# mspfacedraft3.net
KiCad netlist of a schematic drawn in EAGLE
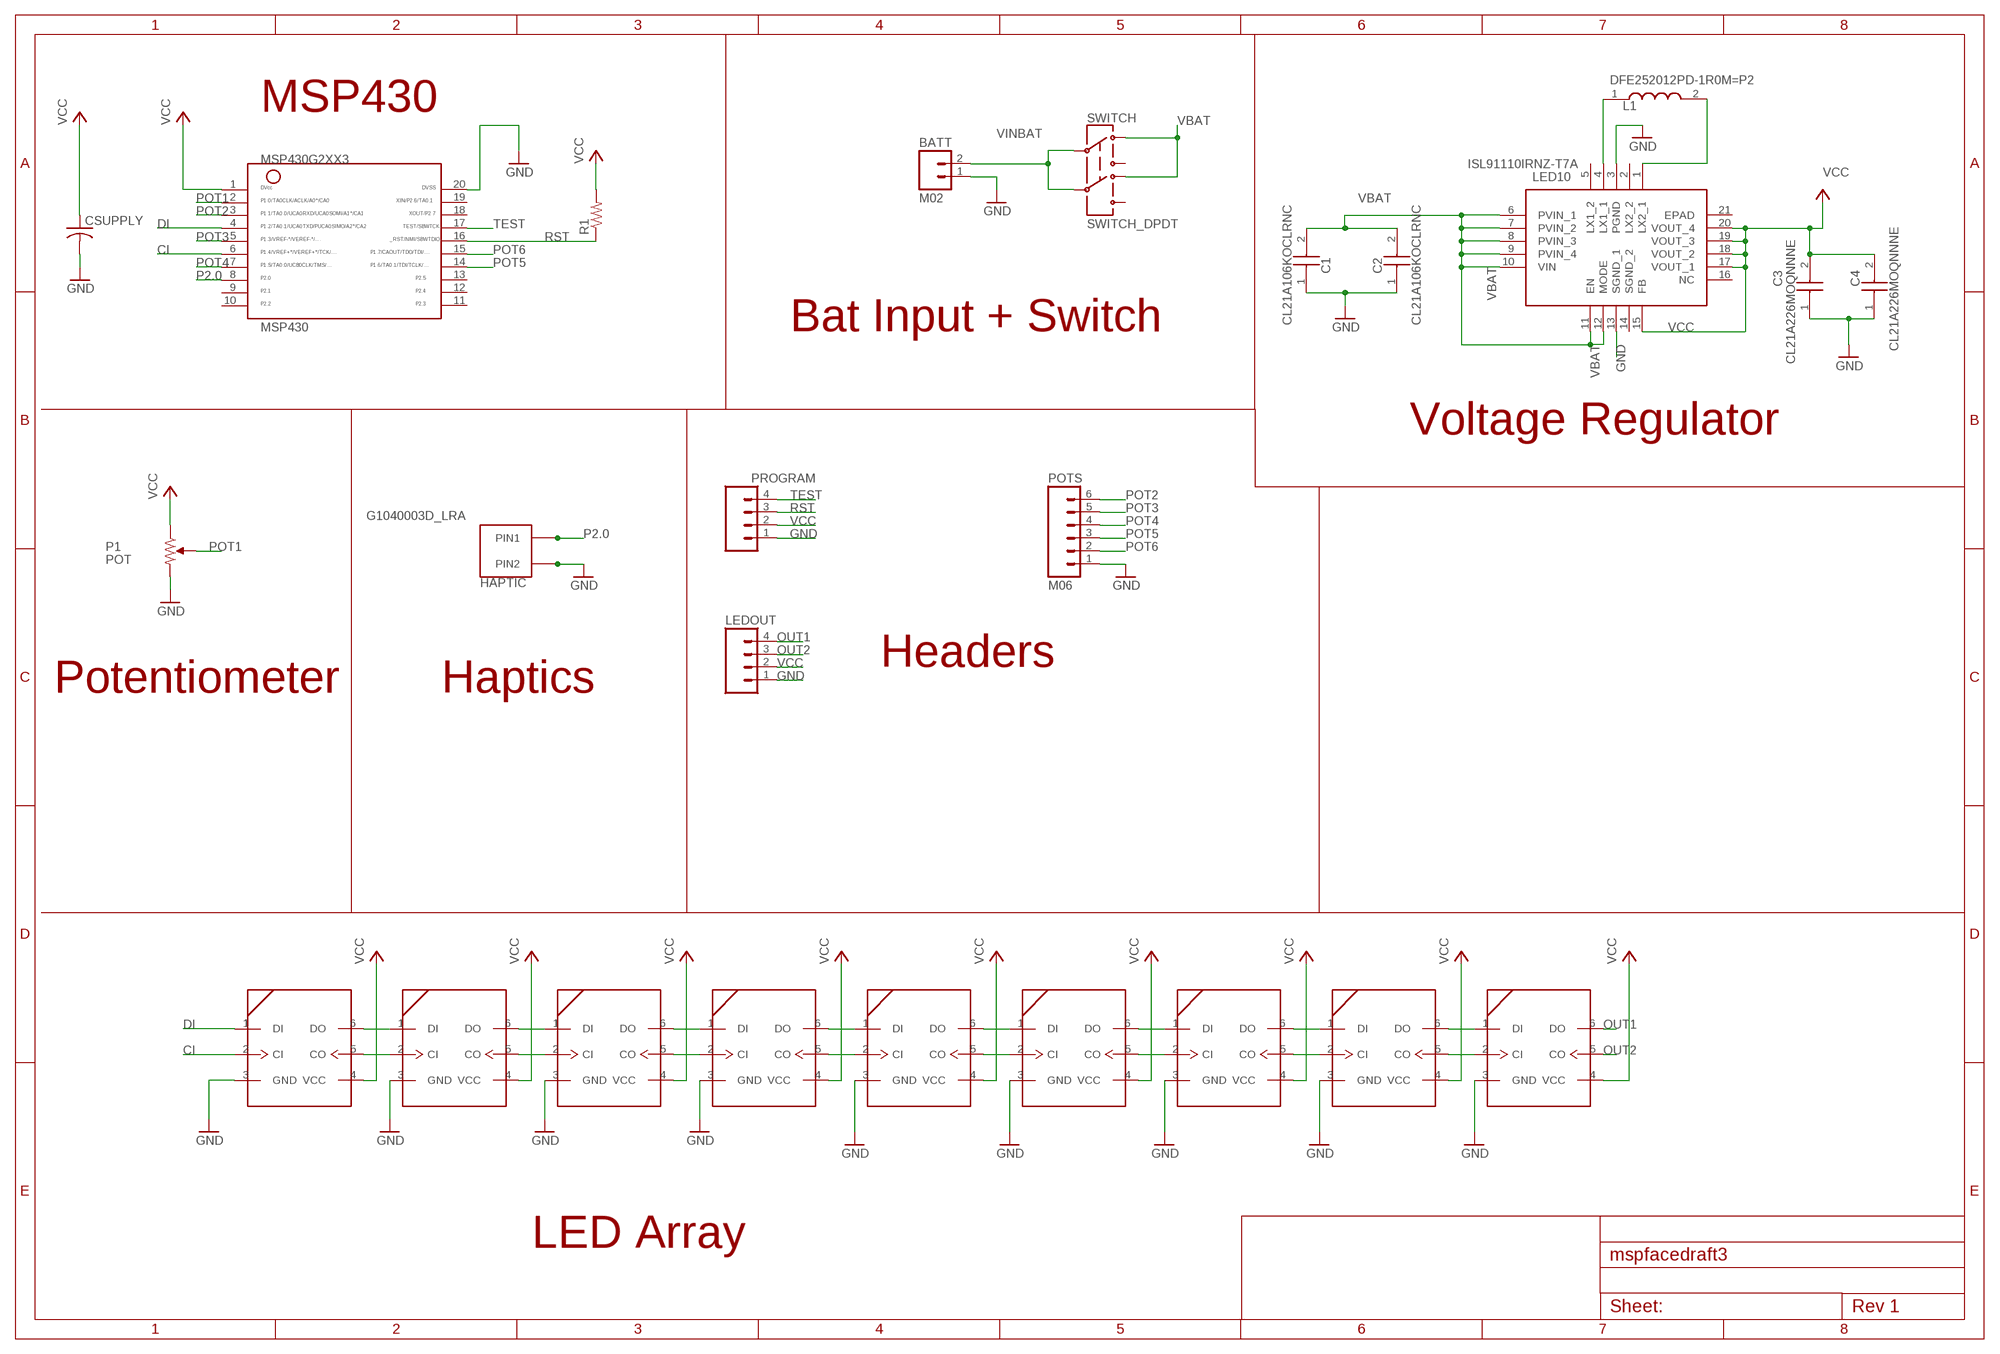
[diagram p0: schematic, sheet 1]

(export (version "E")
  (design (tool "Eeschema 10.0.6"))
  (components
    (comp (ref "BATT")
      (value "M02")
      (footprint "eagle-import:2PINHEADER")
      (libsource (lib "eagle-import") (part "M02"))
    )
    (comp (ref "C1")
      (value "CL21A106KOCLRNC")
      (footprint "eagle-import:CAPC2012X95N")
      (fields (field (name "MOUSER_PART_NUMBER") "187-CL21A106KOCLRNC"))
      (libsource (lib "eagle-import") (part "CL21A106KOCLRNC"))
    )
    (comp (ref "C2")
      (value "CL21A106KOCLRNC")
      (footprint "eagle-import:CAPC2012X95N")
      (fields (field (name "MOUSER_PART_NUMBER") "187-CL21A106KOCLRNC"))
      (libsource (lib "eagle-import") (part "CL21A106KOCLRNC"))
    )
    (comp (ref "C3")
      (value "CL21A226MOQNNNE")
      (footprint "eagle-import:CAPC2012X140N")
      (fields (field (name "MOUSER_PART_NUMBER") "187-CL21A226MOQNNNE"))
      (libsource (lib "eagle-import") (part "CL21A226MOQNNNE"))
    )
    (comp (ref "C4")
      (value "CL21A226MOQNNNE")
      (footprint "eagle-import:CAPC2012X140N")
      (fields (field (name "MOUSER_PART_NUMBER") "187-CL21A226MOQNNNE"))
      (libsource (lib "eagle-import") (part "CL21A226MOQNNNE"))
    )
    (comp (ref "CSUPPLY")
      (value "C-USC1206")
      (footprint "eagle-import:C1206")
      (libsource (lib "eagle-import") (part "C-USC1206"))
    )
    (comp (ref "HAPTIC")
      (value "G1040003D_LRA")
      (footprint "eagle-import:COIN_VIBRATION_MOTOR")
      (libsource (lib "eagle-import") (part "G1040003D_LRA"))
    )
    (comp (ref "L1")
      (value "DFE252012PD-1R0M=P2")
      (footprint "eagle-import:DFE2HCAH1R0MJ0L")
      (fields (field (name "MOUSER_PART_NUMBER") "81-DFE252012PD1R0MP2"))
      (libsource (lib "eagle-import") (part "DFE252012PD-1R0M=P2"))
    )
    (comp (ref "LED1")
      (value "APA102")
      (footprint "eagle-import:5050")
      (libsource (lib "eagle-import") (part "APA102"))
    )
    (comp (ref "LED2")
      (value "APA102")
      (footprint "eagle-import:5050")
      (libsource (lib "eagle-import") (part "APA102"))
    )
    (comp (ref "LED3")
      (value "APA102")
      (footprint "eagle-import:5050")
      (libsource (lib "eagle-import") (part "APA102"))
    )
    (comp (ref "LED4")
      (value "APA102")
      (footprint "eagle-import:5050")
      (libsource (lib "eagle-import") (part "APA102"))
    )
    (comp (ref "LED5")
      (value "APA102")
      (footprint "eagle-import:5050")
      (libsource (lib "eagle-import") (part "APA102"))
    )
    (comp (ref "LED6")
      (value "APA102")
      (footprint "eagle-import:5050")
      (libsource (lib "eagle-import") (part "APA102"))
    )
    (comp (ref "LED7")
      (value "APA102")
      (footprint "eagle-import:5050")
      (libsource (lib "eagle-import") (part "APA102"))
    )
    (comp (ref "LED8")
      (value "APA102")
      (footprint "eagle-import:5050")
      (libsource (lib "eagle-import") (part "APA102"))
    )
    (comp (ref "LED9")
      (value "APA102")
      (footprint "eagle-import:5050")
      (libsource (lib "eagle-import") (part "APA102"))
    )
    (comp (ref "LED10")
      (value "ISL91110IRNZ-T7A")
      (footprint "eagle-import:QFN50P400X400X100-21N")
      (fields (field (name "MOUSER_PART_NUMBER") "968-ISL91110IRNZ-T7A"))
      (libsource (lib "eagle-import") (part "ISL91110IRNZ-T7A"))
    )
    (comp (ref "LEDOUT")
      (value "M04LOCK")
      (footprint "eagle-import:1X04_LOCK")
      (libsource (lib "eagle-import") (part "M04LOCK"))
    )
    (comp (ref "MSP430")
      (value "MSP430G2XX3TSSOP")
      (footprint "eagle-import:PW20")
      (libsource (lib "eagle-import") (part "MSP430G2XX3TSSOP"))
    )
    (comp (ref "P1")
      (value "POT")
      (footprint "eagle-import:POT")
      (libsource (lib "eagle-import") (part "POT"))
    )
    (comp (ref "POTS")
      (value "M06")
      (footprint "eagle-import:6PINHEADER")
      (libsource (lib "eagle-import") (part "M06"))
    )
    (comp (ref "PROGRAM")
      (value "M04LOCK")
      (footprint "eagle-import:1X04_LOCK")
      (libsource (lib "eagle-import") (part "M04LOCK"))
    )
    (comp (ref "R1")
      (value "R-US_R1206")
      (footprint "eagle-import:R1206")
      (libsource (lib "eagle-import") (part "R-US_R1206"))
    )
    (comp (ref "SWITCH")
      (value "SWITCH_DPDT")
      (footprint "eagle-import:JS_DPDT_TH")
      (libsource (lib "eagle-import") (part "SWITCH_DPDT"))
    )
  )
  (nets
    (net (code "1") (name "/CI") (class "Default")
      (node (ref "LED1") (pin "2") (pinfunction "CI_2") (pintype "input"))
      (node (ref "MSP430") (pin "6") (pinfunction "6_6") (pintype "bidirectional"))
    )
    (net (code "2") (name "/DI") (class "Default")
      (node (ref "LED1") (pin "1") (pinfunction "DI_1") (pintype "input"))
      (node (ref "MSP430") (pin "4") (pinfunction "4_4") (pintype "bidirectional"))
    )
    (net (code "3") (name "/OUT1") (class "Default")
      (node (ref "LED9") (pin "6") (pinfunction "DO_6") (pintype "output"))
      (node (ref "LEDOUT") (pin "4") (pinfunction "4_4") (pintype "passive"))
    )
    (net (code "4") (name "/OUT2") (class "Default")
      (node (ref "LED9") (pin "5") (pinfunction "CO_5") (pintype "output"))
      (node (ref "LEDOUT") (pin "3") (pinfunction "3_3") (pintype "passive"))
    )
    (net (code "5") (name "/P2.0") (class "Default")
      (node (ref "HAPTIC") (pin "P$1") (pinfunction "PIN1_P$1") (pintype "bidirectional"))
      (node (ref "MSP430") (pin "8") (pinfunction "8_8") (pintype "bidirectional"))
    )
    (net (code "6") (name "/POT1") (class "Default")
      (node (ref "MSP430") (pin "2") (pinfunction "2_2") (pintype "bidirectional"))
      (node (ref "P1") (pin "SIG") (pinfunction "S_SIG") (pintype "bidirectional"))
    )
    (net (code "7") (name "/POT2") (class "Default")
      (node (ref "MSP430") (pin "3") (pinfunction "3_3") (pintype "bidirectional"))
      (node (ref "POTS") (pin "6") (pinfunction "6_6") (pintype "passive"))
    )
    (net (code "8") (name "/POT3") (class "Default")
      (node (ref "MSP430") (pin "5") (pinfunction "5_5") (pintype "bidirectional"))
      (node (ref "POTS") (pin "5") (pinfunction "5_5") (pintype "passive"))
    )
    (net (code "9") (name "/POT4") (class "Default")
      (node (ref "MSP430") (pin "7") (pinfunction "7_7") (pintype "bidirectional"))
      (node (ref "POTS") (pin "4") (pinfunction "4_4") (pintype "passive"))
    )
    (net (code "10") (name "/POT5") (class "Default")
      (node (ref "MSP430") (pin "14") (pinfunction "14_14") (pintype "bidirectional"))
      (node (ref "POTS") (pin "3") (pinfunction "3_3") (pintype "passive"))
    )
    (net (code "11") (name "/POT6") (class "Default")
      (node (ref "MSP430") (pin "15") (pinfunction "15_15") (pintype "bidirectional"))
      (node (ref "POTS") (pin "2") (pinfunction "2_2") (pintype "passive"))
    )
    (net (code "12") (name "/RST") (class "Default")
      (node (ref "MSP430") (pin "16") (pinfunction "16_16") (pintype "bidirectional"))
      (node (ref "PROGRAM") (pin "3") (pinfunction "3_3") (pintype "passive"))
      (node (ref "R1") (pin "1") (pinfunction "1_1") (pintype "passive"))
    )
    (net (code "13") (name "/TEST") (class "Default")
      (node (ref "MSP430") (pin "17") (pinfunction "17_17") (pintype "bidirectional"))
      (node (ref "PROGRAM") (pin "4") (pinfunction "4_4") (pintype "passive"))
    )
    (net (code "14") (name "/VBAT") (class "Default")
      (node (ref "C1") (pin "2") (pinfunction "2_2") (pintype "bidirectional"))
      (node (ref "C2") (pin "2") (pinfunction "2_2") (pintype "bidirectional"))
      (node (ref "LED10") (pin "10") (pinfunction "VIN_10") (pintype "bidirectional"))
      (node (ref "LED10") (pin "11") (pinfunction "EN_11") (pintype "bidirectional"))
      (node (ref "LED10") (pin "12") (pinfunction "MODE_12") (pintype "bidirectional"))
      (node (ref "LED10") (pin "6") (pinfunction "PVIN_1_6") (pintype "bidirectional"))
      (node (ref "LED10") (pin "7") (pinfunction "PVIN_2_7") (pintype "bidirectional"))
      (node (ref "LED10") (pin "8") (pinfunction "PVIN_3_8") (pintype "bidirectional"))
      (node (ref "LED10") (pin "9") (pinfunction "PVIN_4_9") (pintype "bidirectional"))
      (node (ref "SWITCH") (pin "1") (pinfunction "1_1") (pintype "bidirectional"))
      (node (ref "SWITCH") (pin "4") (pinfunction "4_4") (pintype "bidirectional"))
    )
    (net (code "15") (name "/VINBAT") (class "Default")
      (node (ref "BATT") (pin "2") (pinfunction "2_2") (pintype "passive"))
      (node (ref "SWITCH") (pin "2") (pinfunction "2_2") (pintype "bidirectional"))
      (node (ref "SWITCH") (pin "5") (pinfunction "5_5") (pintype "bidirectional"))
    )
    (net (code "16") (name "GND") (class "Default")
      (node (ref "BATT") (pin "1") (pinfunction "1_1") (pintype "passive"))
      (node (ref "C1") (pin "1") (pinfunction "1_1") (pintype "bidirectional"))
      (node (ref "C2") (pin "1") (pinfunction "1_1") (pintype "bidirectional"))
      (node (ref "C3") (pin "1") (pinfunction "1_1") (pintype "bidirectional"))
      (node (ref "C4") (pin "1") (pinfunction "1_1") (pintype "bidirectional"))
      (node (ref "CSUPPLY") (pin "2") (pinfunction "2_2") (pintype "passive"))
      (node (ref "HAPTIC") (pin "P$2") (pinfunction "PIN2_P$2") (pintype "bidirectional"))
      (node (ref "LED1") (pin "3") (pinfunction "GND_3") (pintype "power_in"))
      (node (ref "LED10") (pin "13") (pinfunction "SGND_1_13") (pintype "bidirectional"))
      (node (ref "LED10") (pin "3") (pinfunction "PGND_3") (pintype "bidirectional"))
      (node (ref "LED2") (pin "3") (pinfunction "GND_3") (pintype "power_in"))
      (node (ref "LED3") (pin "3") (pinfunction "GND_3") (pintype "power_in"))
      (node (ref "LED4") (pin "3") (pinfunction "GND_3") (pintype "power_in"))
      (node (ref "LED5") (pin "3") (pinfunction "GND_3") (pintype "power_in"))
      (node (ref "LED6") (pin "3") (pinfunction "GND_3") (pintype "power_in"))
      (node (ref "LED7") (pin "3") (pinfunction "GND_3") (pintype "power_in"))
      (node (ref "LED8") (pin "3") (pinfunction "GND_3") (pintype "power_in"))
      (node (ref "LED9") (pin "3") (pinfunction "GND_3") (pintype "power_in"))
      (node (ref "LEDOUT") (pin "1") (pinfunction "1_1") (pintype "passive"))
      (node (ref "MSP430") (pin "20") (pinfunction "20_20") (pintype "bidirectional"))
      (node (ref "P1") (pin "GND") (pinfunction "CW_GND") (pintype "passive"))
      (node (ref "POTS") (pin "1") (pinfunction "1_1") (pintype "passive"))
      (node (ref "PROGRAM") (pin "1") (pinfunction "1_1") (pintype "passive"))
    )
    (net (code "17") (name "Net-(LED1-CO)") (class "Default")
      (node (ref "LED1") (pin "5") (pinfunction "CO_5") (pintype "output"))
      (node (ref "LED2") (pin "2") (pinfunction "CI_2") (pintype "input"))
    )
    (net (code "18") (name "Net-(LED1-DO)") (class "Default")
      (node (ref "LED1") (pin "6") (pinfunction "DO_6") (pintype "output"))
      (node (ref "LED2") (pin "1") (pinfunction "DI_1") (pintype "input"))
    )
    (net (code "19") (name "Net-(LED2-CO)") (class "Default")
      (node (ref "LED2") (pin "5") (pinfunction "CO_5") (pintype "output"))
      (node (ref "LED3") (pin "2") (pinfunction "CI_2") (pintype "input"))
    )
    (net (code "20") (name "Net-(LED2-DO)") (class "Default")
      (node (ref "LED2") (pin "6") (pinfunction "DO_6") (pintype "output"))
      (node (ref "LED3") (pin "1") (pinfunction "DI_1") (pintype "input"))
    )
    (net (code "21") (name "Net-(LED3-CO)") (class "Default")
      (node (ref "LED3") (pin "5") (pinfunction "CO_5") (pintype "output"))
      (node (ref "LED4") (pin "2") (pinfunction "CI_2") (pintype "input"))
    )
    (net (code "22") (name "Net-(LED3-DO)") (class "Default")
      (node (ref "LED3") (pin "6") (pinfunction "DO_6") (pintype "output"))
      (node (ref "LED4") (pin "1") (pinfunction "DI_1") (pintype "input"))
    )
    (net (code "23") (name "Net-(LED4-CO)") (class "Default")
      (node (ref "LED4") (pin "5") (pinfunction "CO_5") (pintype "output"))
      (node (ref "LED5") (pin "2") (pinfunction "CI_2") (pintype "input"))
    )
    (net (code "24") (name "Net-(LED4-DO)") (class "Default")
      (node (ref "LED4") (pin "6") (pinfunction "DO_6") (pintype "output"))
      (node (ref "LED5") (pin "1") (pinfunction "DI_1") (pintype "input"))
    )
    (net (code "25") (name "Net-(LED5-CO)") (class "Default")
      (node (ref "LED5") (pin "5") (pinfunction "CO_5") (pintype "output"))
      (node (ref "LED6") (pin "2") (pinfunction "CI_2") (pintype "input"))
    )
    (net (code "26") (name "Net-(LED5-DO)") (class "Default")
      (node (ref "LED5") (pin "6") (pinfunction "DO_6") (pintype "output"))
      (node (ref "LED6") (pin "1") (pinfunction "DI_1") (pintype "input"))
    )
    (net (code "27") (name "Net-(LED6-CO)") (class "Default")
      (node (ref "LED6") (pin "5") (pinfunction "CO_5") (pintype "output"))
      (node (ref "LED7") (pin "2") (pinfunction "CI_2") (pintype "input"))
    )
    (net (code "28") (name "Net-(LED6-DO)") (class "Default")
      (node (ref "LED6") (pin "6") (pinfunction "DO_6") (pintype "output"))
      (node (ref "LED7") (pin "1") (pinfunction "DI_1") (pintype "input"))
    )
    (net (code "29") (name "Net-(LED7-CO)") (class "Default")
      (node (ref "LED7") (pin "5") (pinfunction "CO_5") (pintype "output"))
      (node (ref "LED8") (pin "2") (pinfunction "CI_2") (pintype "input"))
    )
    (net (code "30") (name "Net-(LED7-DO)") (class "Default")
      (node (ref "LED7") (pin "6") (pinfunction "DO_6") (pintype "output"))
      (node (ref "LED8") (pin "1") (pinfunction "DI_1") (pintype "input"))
    )
    (net (code "31") (name "Net-(LED8-CO)") (class "Default")
      (node (ref "LED8") (pin "5") (pinfunction "CO_5") (pintype "output"))
      (node (ref "LED9") (pin "2") (pinfunction "CI_2") (pintype "input"))
    )
    (net (code "32") (name "Net-(LED8-DO)") (class "Default")
      (node (ref "LED8") (pin "6") (pinfunction "DO_6") (pintype "output"))
      (node (ref "LED9") (pin "1") (pinfunction "DI_1") (pintype "input"))
    )
    (net (code "33") (name "Net-(LED10-LX1_1)") (class "Default")
      (node (ref "L1") (pin "1") (pinfunction "1_1") (pintype "bidirectional"))
      (node (ref "LED10") (pin "4") (pinfunction "LX1_1_4") (pintype "bidirectional"))
    )
    (net (code "34") (name "Net-(LED10-LX2_1)") (class "Default")
      (node (ref "L1") (pin "2") (pinfunction "2_2") (pintype "bidirectional"))
      (node (ref "LED10") (pin "1") (pinfunction "LX2_1_1") (pintype "bidirectional"))
    )
    (net (code "35") (name "VCC") (class "Default")
      (node (ref "C3") (pin "2") (pinfunction "2_2") (pintype "bidirectional"))
      (node (ref "C4") (pin "2") (pinfunction "2_2") (pintype "bidirectional"))
      (node (ref "CSUPPLY") (pin "1") (pinfunction "1_1") (pintype "passive"))
      (node (ref "LED1") (pin "4") (pinfunction "VCC_4") (pintype "power_in"))
      (node (ref "LED10") (pin "15") (pinfunction "FB_15") (pintype "bidirectional"))
      (node (ref "LED10") (pin "17") (pinfunction "VOUT_1_17") (pintype "bidirectional"))
      (node (ref "LED10") (pin "18") (pinfunction "VOUT_2_18") (pintype "bidirectional"))
      (node (ref "LED10") (pin "19") (pinfunction "VOUT_3_19") (pintype "bidirectional"))
      (node (ref "LED10") (pin "20") (pinfunction "VOUT_4_20") (pintype "bidirectional"))
      (node (ref "LED2") (pin "4") (pinfunction "VCC_4") (pintype "power_in"))
      (node (ref "LED3") (pin "4") (pinfunction "VCC_4") (pintype "power_in"))
      (node (ref "LED4") (pin "4") (pinfunction "VCC_4") (pintype "power_in"))
      (node (ref "LED5") (pin "4") (pinfunction "VCC_4") (pintype "power_in"))
      (node (ref "LED6") (pin "4") (pinfunction "VCC_4") (pintype "power_in"))
      (node (ref "LED7") (pin "4") (pinfunction "VCC_4") (pintype "power_in"))
      (node (ref "LED8") (pin "4") (pinfunction "VCC_4") (pintype "power_in"))
      (node (ref "LED9") (pin "4") (pinfunction "VCC_4") (pintype "power_in"))
      (node (ref "LEDOUT") (pin "2") (pinfunction "2_2") (pintype "passive"))
      (node (ref "MSP430") (pin "1") (pinfunction "1_1") (pintype "bidirectional"))
      (node (ref "P1") (pin "VDD") (pinfunction "CCW_VDD") (pintype "passive"))
      (node (ref "PROGRAM") (pin "2") (pinfunction "2_2") (pintype "passive"))
      (node (ref "R1") (pin "2") (pinfunction "2_2") (pintype "passive"))
    )
    (net (code "36") (name "unconnected-(LED10-EPAD-Pad21)") (class "Default")
      (node (ref "LED10") (pin "21") (pinfunction "EPAD_21") (pintype "bidirectional"))
    )
    (net (code "37") (name "unconnected-(LED10-LX1_2-Pad5)") (class "Default")
      (node (ref "LED10") (pin "5") (pinfunction "LX1_2_5") (pintype "bidirectional"))
    )
    (net (code "38") (name "unconnected-(LED10-LX2_2-Pad2)") (class "Default")
      (node (ref "LED10") (pin "2") (pinfunction "LX2_2_2") (pintype "bidirectional"))
    )
    (net (code "39") (name "unconnected-(LED10-NC-Pad16)") (class "Default")
      (node (ref "LED10") (pin "16") (pinfunction "NC_16") (pintype "no_connect"))
    )
    (net (code "40") (name "unconnected-(LED10-SGND_2-Pad14)") (class "Default")
      (node (ref "LED10") (pin "14") (pinfunction "SGND_2_14") (pintype "bidirectional"))
    )
    (net (code "41") (name "unconnected-(MSP430-Pad9)") (class "Default")
      (node (ref "MSP430") (pin "9") (pinfunction "9_9") (pintype "bidirectional"))
    )
    (net (code "42") (name "unconnected-(MSP430-Pad10)") (class "Default")
      (node (ref "MSP430") (pin "10") (pinfunction "10_10") (pintype "bidirectional"))
    )
    (net (code "43") (name "unconnected-(MSP430-Pad11)") (class "Default")
      (node (ref "MSP430") (pin "11") (pinfunction "11_11") (pintype "bidirectional"))
    )
    (net (code "44") (name "unconnected-(MSP430-Pad12)") (class "Default")
      (node (ref "MSP430") (pin "12") (pinfunction "12_12") (pintype "bidirectional"))
    )
    (net (code "45") (name "unconnected-(MSP430-Pad13)") (class "Default")
      (node (ref "MSP430") (pin "13") (pinfunction "13_13") (pintype "bidirectional"))
    )
    (net (code "46") (name "unconnected-(MSP430-Pad18)") (class "Default")
      (node (ref "MSP430") (pin "18") (pinfunction "18_18") (pintype "bidirectional"))
    )
    (net (code "47") (name "unconnected-(MSP430-Pad19)") (class "Default")
      (node (ref "MSP430") (pin "19") (pinfunction "19_19") (pintype "bidirectional"))
    )
    (net (code "48") (name "unconnected-(SWITCH-Pad3)") (class "Default")
      (node (ref "SWITCH") (pin "3") (pinfunction "3_3") (pintype "bidirectional"))
    )
    (net (code "49") (name "unconnected-(SWITCH-Pad6)") (class "Default")
      (node (ref "SWITCH") (pin "6") (pinfunction "6_6") (pintype "bidirectional"))
    )
  )
)
